# ADDER.net
KiCad netlist of a schematic drawn in Altium Designer
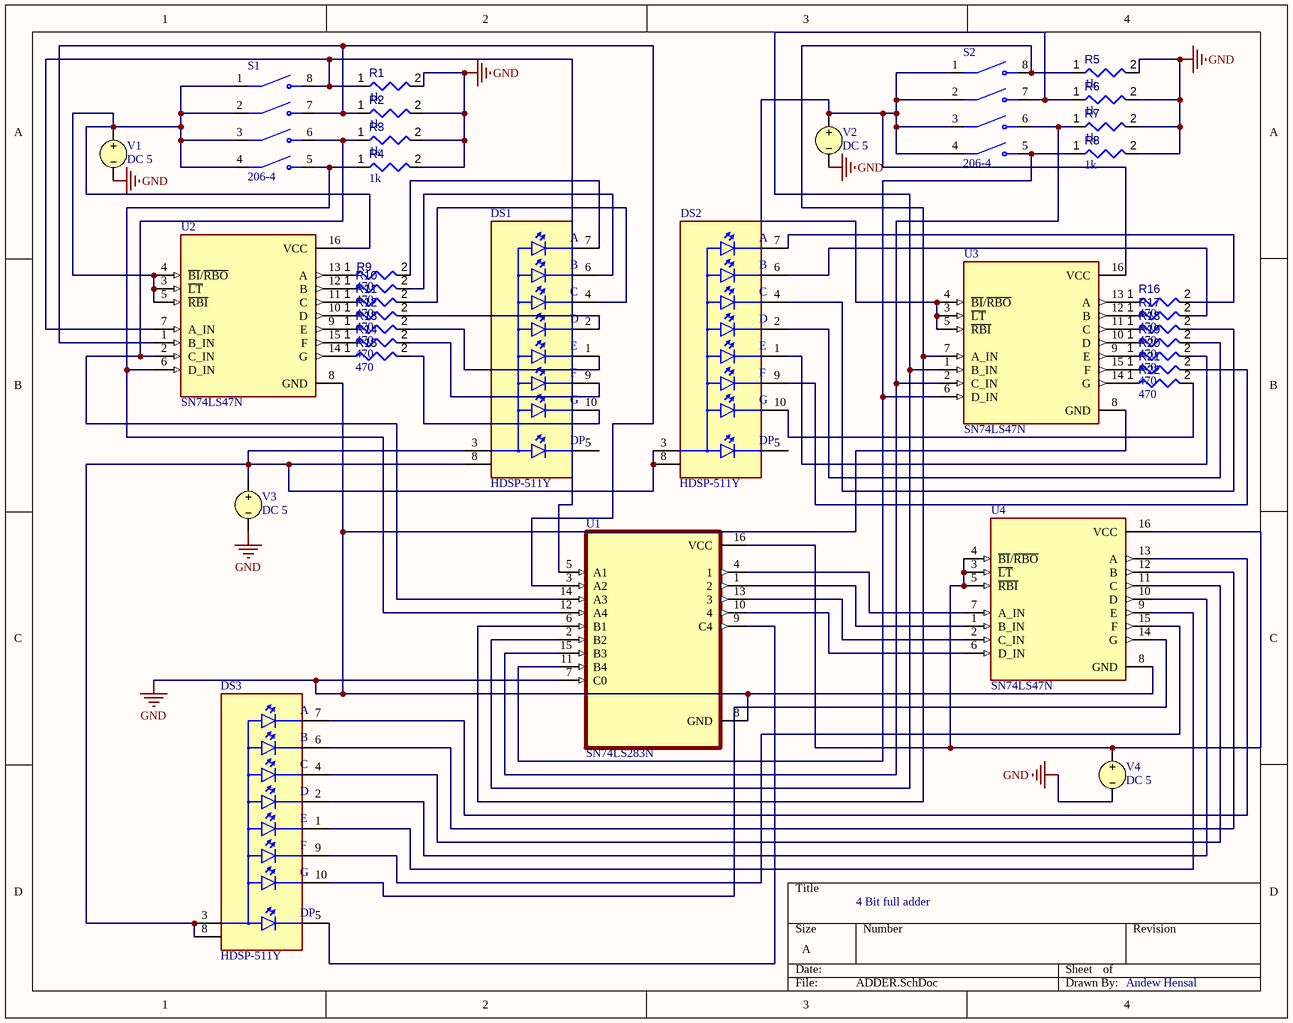
[diagram p0: ADDER.SchDoc]

(export (version "E")
  (design (tool "Eeschema 10.0.6"))
  (components
    (comp (ref "DS1")
      (value "HDSP-511Y")
      (footprint "LED_HDSP-511Y")
      (fields (field (name "MF") "Broadcom Limited"))
      (libsource (lib "HDSP-511Y") (part "HDSP-511Y"))
    )
    (comp (ref "DS2")
      (value "HDSP-511Y")
      (footprint "LED_HDSP-511Y")
      (fields (field (name "MF") "Broadcom Limited"))
      (libsource (lib "HDSP-511Y") (part "HDSP-511Y"))
    )
    (comp (ref "DS3")
      (value "HDSP-511Y")
      (footprint "LED_HDSP-511Y")
      (fields (field (name "MF") "Broadcom Limited"))
      (libsource (lib "HDSP-511Y") (part "HDSP-511Y"))
    )
    (comp (ref "R1")
      (value "1k")
      (footprint "RESC0805(2012)_L")
      (description "Chip Resistor, 1 kOhms, +/-5%, 125 mW, -55 to 155 degC, 0805")
      (fields (field (name "TOLERANCE") "5%") (field (name "POWER") "125mW"))
      (libsource (lib "Andrew Hensal") (part "RES-2"))
    )
    (comp (ref "R2")
      (value "1k")
      (footprint "RESC0805(2012)_L")
      (description "Chip Resistor, 1 kOhms, +/-5%, 125 mW, -55 to 155 degC, 0805")
      (fields (field (name "TOLERANCE") "5%") (field (name "POWER") "125mW"))
      (libsource (lib "Andrew Hensal") (part "RES-2"))
    )
    (comp (ref "R3")
      (value "1k")
      (footprint "RESC0805(2012)_L")
      (description "Chip Resistor, 1 kOhms, +/-5%, 125 mW, -55 to 155 degC, 0805")
      (fields (field (name "TOLERANCE") "5%") (field (name "POWER") "125mW"))
      (libsource (lib "Andrew Hensal") (part "RES-2"))
    )
    (comp (ref "R4")
      (value "1k")
      (footprint "RESC0805(2012)_L")
      (description "Chip Resistor, 1 kOhms, +/-5%, 125 mW, -55 to 155 degC, 0805")
      (fields (field (name "TOLERANCE") "5%") (field (name "POWER") "125mW"))
      (libsource (lib "Andrew Hensal") (part "RES-2"))
    )
    (comp (ref "R5")
      (value "1k")
      (footprint "RESC0805(2012)_L")
      (description "Chip Resistor, 1 kOhms, +/-5%, 125 mW, -55 to 155 degC, 0805")
      (fields (field (name "TOLERANCE") "5%") (field (name "POWER") "125mW"))
      (libsource (lib "Andrew Hensal") (part "RES-2"))
    )
    (comp (ref "R6")
      (value "1k")
      (footprint "RESC0805(2012)_L")
      (description "Chip Resistor, 1 kOhms, +/-5%, 125 mW, -55 to 155 degC, 0805")
      (fields (field (name "TOLERANCE") "5%") (field (name "POWER") "125mW"))
      (libsource (lib "Andrew Hensal") (part "RES-2"))
    )
    (comp (ref "R7")
      (value "1k")
      (footprint "RESC0805(2012)_L")
      (description "Chip Resistor, 1 kOhms, +/-5%, 125 mW, -55 to 155 degC, 0805")
      (fields (field (name "TOLERANCE") "5%") (field (name "POWER") "125mW"))
      (libsource (lib "Andrew Hensal") (part "RES-2"))
    )
    (comp (ref "R8")
      (value "1k")
      (footprint "RESC0805(2012)_L")
      (description "Chip Resistor, 1 kOhms, +/-5%, 125 mW, -55 to 155 degC, 0805")
      (fields (field (name "TOLERANCE") "5%") (field (name "POWER") "125mW"))
      (libsource (lib "Andrew Hensal") (part "RES-2"))
    )
    (comp (ref "R9")
      (value "470")
      (footprint "RESC0805(2012)_L")
      (description "Chip Resistor, 470 Ohms, +/-5%, 125 mW, -55 to 155 degC, 0805")
      (fields (field (name "TOLERANCE") "5%") (field (name "POWER") "125mW"))
      (libsource (lib "Andrew Hensal") (part "RES-2"))
    )
    (comp (ref "R10")
      (value "470")
      (footprint "RESC0805(2012)_L")
      (description "Chip Resistor, 470 Ohms, +/-5%, 125 mW, -55 to 155 degC, 0805")
      (fields (field (name "TOLERANCE") "5%") (field (name "POWER") "125mW"))
      (libsource (lib "Andrew Hensal") (part "RES-2"))
    )
    (comp (ref "R11")
      (value "470")
      (footprint "RESC0805(2012)_L")
      (description "Chip Resistor, 470 Ohms, +/-5%, 125 mW, -55 to 155 degC, 0805")
      (fields (field (name "TOLERANCE") "5%") (field (name "POWER") "125mW"))
      (libsource (lib "Andrew Hensal") (part "RES-2"))
    )
    (comp (ref "R12")
      (value "470")
      (footprint "RESC0805(2012)_L")
      (description "Chip Resistor, 470 Ohms, +/-5%, 125 mW, -55 to 155 degC, 0805")
      (fields (field (name "TOLERANCE") "5%") (field (name "POWER") "125mW"))
      (libsource (lib "Andrew Hensal") (part "RES-2"))
    )
    (comp (ref "R13")
      (value "470")
      (footprint "RESC0805(2012)_L")
      (description "Chip Resistor, 470 Ohms, +/-5%, 125 mW, -55 to 155 degC, 0805")
      (fields (field (name "TOLERANCE") "5%") (field (name "POWER") "125mW"))
      (libsource (lib "Andrew Hensal") (part "RES-2"))
    )
    (comp (ref "R14")
      (value "470")
      (footprint "RESC0805(2012)_L")
      (description "Chip Resistor, 470 Ohms, +/-5%, 125 mW, -55 to 155 degC, 0805")
      (fields (field (name "TOLERANCE") "5%") (field (name "POWER") "125mW"))
      (libsource (lib "Andrew Hensal") (part "RES-2"))
    )
    (comp (ref "R15")
      (value "470")
      (footprint "RESC0805(2012)_L")
      (description "Chip Resistor, 470 Ohms, +/-5%, 125 mW, -55 to 155 degC, 0805")
      (fields (field (name "TOLERANCE") "5%") (field (name "POWER") "125mW"))
      (libsource (lib "Andrew Hensal") (part "RES-2"))
    )
    (comp (ref "R16")
      (value "470")
      (footprint "RESC0805(2012)_L")
      (description "Chip Resistor, 470 Ohms, +/-5%, 125 mW, -55 to 155 degC, 0805")
      (fields (field (name "TOLERANCE") "5%") (field (name "POWER") "125mW"))
      (libsource (lib "Andrew Hensal") (part "RES-2"))
    )
    (comp (ref "R17")
      (value "470")
      (footprint "RESC0805(2012)_L")
      (description "Chip Resistor, 470 Ohms, +/-5%, 125 mW, -55 to 155 degC, 0805")
      (fields (field (name "TOLERANCE") "5%") (field (name "POWER") "125mW"))
      (libsource (lib "Andrew Hensal") (part "RES-2"))
    )
    (comp (ref "R18")
      (value "470")
      (footprint "RESC0805(2012)_L")
      (description "Chip Resistor, 470 Ohms, +/-5%, 125 mW, -55 to 155 degC, 0805")
      (fields (field (name "TOLERANCE") "5%") (field (name "POWER") "125mW"))
      (libsource (lib "Andrew Hensal") (part "RES-2"))
    )
    (comp (ref "R19")
      (value "470")
      (footprint "RESC0805(2012)_L")
      (description "Chip Resistor, 470 Ohms, +/-5%, 125 mW, -55 to 155 degC, 0805")
      (fields (field (name "TOLERANCE") "5%") (field (name "POWER") "125mW"))
      (libsource (lib "Andrew Hensal") (part "RES-2"))
    )
    (comp (ref "R20")
      (value "470")
      (footprint "RESC0805(2012)_L")
      (description "Chip Resistor, 470 Ohms, +/-5%, 125 mW, -55 to 155 degC, 0805")
      (fields (field (name "TOLERANCE") "5%") (field (name "POWER") "125mW"))
      (libsource (lib "Andrew Hensal") (part "RES-2"))
    )
    (comp (ref "R21")
      (value "470")
      (footprint "RESC0805(2012)_L")
      (description "Chip Resistor, 470 Ohms, +/-5%, 125 mW, -55 to 155 degC, 0805")
      (fields (field (name "TOLERANCE") "5%") (field (name "POWER") "125mW"))
      (libsource (lib "Andrew Hensal") (part "RES-2"))
    )
    (comp (ref "R22")
      (value "470")
      (footprint "RESC0805(2012)_L")
      (description "Chip Resistor, 470 Ohms, +/-5%, 125 mW, -55 to 155 degC, 0805")
      (fields (field (name "TOLERANCE") "5%") (field (name "POWER") "125mW"))
      (libsource (lib "Andrew Hensal") (part "RES-2"))
    )
    (comp (ref "S1")
      (value "206-4")
      (footprint "SW_206-4")
      (fields (field (name "MF") "{'manufacturer': u'CTS Components'}"))
      (libsource (lib "206-4") (part "206-4"))
    )
    (comp (ref "S2")
      (value "206-4")
      (footprint "SW_206-4")
      (fields (field (name "MF") "{'manufacturer': u'CTS Components'}"))
      (libsource (lib "206-4") (part "206-4"))
    )
    (comp (ref "U1")
      (value "SN74LS283N")
      (footprint "DIP794W45P254L1969H508Q16")
      (description "4-Bit Binary Full Adders With Fast Carry 16-PDIP 0 to 70")
      (fields (field (name "MF") "Texas Instruments"))
      (libsource (lib "SN74LS283N") (part "SN74LS283N"))
    )
    (comp (ref "U2")
      (value "SN74LS47N")
      (footprint "DIP794W45P254L1930H508Q16")
      (description "BCD-to-Seven-Segment Decoders/Drivers")
      (fields (field (name "MF") "Texas Instruments"))
      (libsource (lib "SN74LS47N") (part "SN74LS47N"))
    )
    (comp (ref "U3")
      (value "SN74LS47N")
      (footprint "DIP794W45P254L1930H508Q16")
      (description "BCD-to-Seven-Segment Decoders/Drivers")
      (fields (field (name "MF") "Texas Instruments"))
      (libsource (lib "SN74LS47N") (part "SN74LS47N"))
    )
    (comp (ref "U4")
      (value "SN74LS47N")
      (footprint "DIP794W45P254L1930H508Q16")
      (description "BCD-to-Seven-Segment Decoders/Drivers")
      (fields (field (name "MF") "Texas Instruments"))
      (libsource (lib "SN74LS47N") (part "SN74LS47N"))
    )
    (comp (ref "V1")
      (value "DC 5")
      (description "Voltage Source")
      (fields (field (name "PUBLISHER") "Altium Limited"))
      (libsource (lib "Simulation Generic Components") (part "VSRC"))
    )
    (comp (ref "V2")
      (value "DC 5")
      (description "Voltage Source")
      (fields (field (name "PUBLISHER") "Altium Limited"))
      (libsource (lib "Simulation Generic Components") (part "VSRC"))
    )
    (comp (ref "V3")
      (value "DC 5")
      (description "Voltage Source")
      (fields (field (name "PUBLISHER") "Altium Limited"))
      (libsource (lib "Simulation Generic Components") (part "VSRC"))
    )
    (comp (ref "V4")
      (value "DC 5")
      (description "Voltage Source")
      (fields (field (name "PUBLISHER") "Altium Limited"))
      (libsource (lib "Simulation Generic Components") (part "VSRC"))
    )
  )
  (nets
    (net (code "1") (name "GND") (class "Default")
      (node (ref "R1") (pin "2") (pinfunction "2_2") (pintype "passive"))
      (node (ref "R2") (pin "2") (pinfunction "2_2") (pintype "passive"))
      (node (ref "R3") (pin "2") (pinfunction "2_2") (pintype "passive"))
      (node (ref "R4") (pin "2") (pinfunction "2_2") (pintype "passive"))
      (node (ref "R5") (pin "2") (pinfunction "2_2") (pintype "passive"))
      (node (ref "R6") (pin "2") (pinfunction "2_2") (pintype "passive"))
      (node (ref "R7") (pin "2") (pinfunction "2_2") (pintype "passive"))
      (node (ref "R8") (pin "2") (pinfunction "2_2") (pintype "passive"))
      (node (ref "U1") (pin "7") (pinfunction "C0_7") (pintype "input"))
      (node (ref "U1") (pin "8") (pinfunction "GND_8") (pintype "power_in"))
      (node (ref "U2") (pin "8") (pinfunction "GND_8") (pintype "power_in"))
      (node (ref "U3") (pin "8") (pinfunction "GND_8") (pintype "power_in"))
      (node (ref "U4") (pin "8") (pinfunction "GND_8") (pintype "power_in"))
      (node (ref "V1") (pin "2") (pinfunction "2_2") (pintype "passive"))
      (node (ref "V2") (pin "2") (pinfunction "2_2") (pintype "passive"))
      (node (ref "V3") (pin "2") (pinfunction "2_2") (pintype "passive"))
      (node (ref "V4") (pin "2") (pinfunction "2_2") (pintype "passive"))
    )
    (net (code "2") (name "Net-(DS1-A)") (class "Default")
      (node (ref "DS1") (pin "7") (pinfunction "A_7") (pintype "passive"))
      (node (ref "R9") (pin "2") (pinfunction "2_2") (pintype "passive"))
    )
    (net (code "3") (name "Net-(DS1-B)") (class "Default")
      (node (ref "DS1") (pin "6") (pinfunction "B_6") (pintype "passive"))
      (node (ref "R10") (pin "2") (pinfunction "2_2") (pintype "passive"))
    )
    (net (code "4") (name "Net-(DS1-C)") (class "Default")
      (node (ref "DS1") (pin "4") (pinfunction "C_4") (pintype "passive"))
      (node (ref "R11") (pin "2") (pinfunction "2_2") (pintype "passive"))
    )
    (net (code "5") (name "Net-(DS1-COM-Pad3)") (class "Default")
      (node (ref "DS1") (pin "3") (pinfunction "COM_3") (pintype "passive"))
      (node (ref "DS1") (pin "8") (pinfunction "COM_8") (pintype "passive"))
      (node (ref "DS2") (pin "3") (pinfunction "COM_3") (pintype "passive"))
      (node (ref "DS2") (pin "8") (pinfunction "COM_8") (pintype "passive"))
      (node (ref "DS3") (pin "3") (pinfunction "COM_3") (pintype "passive"))
      (node (ref "DS3") (pin "8") (pinfunction "COM_8") (pintype "passive"))
      (node (ref "V3") (pin "1") (pinfunction "1_1") (pintype "passive"))
    )
    (net (code "6") (name "Net-(DS1-D)") (class "Default")
      (node (ref "DS1") (pin "2") (pinfunction "D_2") (pintype "passive"))
      (node (ref "R12") (pin "2") (pinfunction "2_2") (pintype "passive"))
    )
    (net (code "7") (name "Net-(DS1-E)") (class "Default")
      (node (ref "DS1") (pin "1") (pinfunction "E_1") (pintype "passive"))
      (node (ref "R13") (pin "2") (pinfunction "2_2") (pintype "passive"))
    )
    (net (code "8") (name "Net-(DS1-F)") (class "Default")
      (node (ref "DS1") (pin "9") (pinfunction "F_9") (pintype "passive"))
      (node (ref "R14") (pin "2") (pinfunction "2_2") (pintype "passive"))
    )
    (net (code "9") (name "Net-(DS1-G)") (class "Default")
      (node (ref "DS1") (pin "10") (pinfunction "G_10") (pintype "passive"))
      (node (ref "R15") (pin "2") (pinfunction "2_2") (pintype "passive"))
    )
    (net (code "10") (name "Net-(DS2-A)") (class "Default")
      (node (ref "DS2") (pin "7") (pinfunction "A_7") (pintype "passive"))
      (node (ref "R16") (pin "2") (pinfunction "2_2") (pintype "passive"))
    )
    (net (code "11") (name "Net-(DS2-B)") (class "Default")
      (node (ref "DS2") (pin "6") (pinfunction "B_6") (pintype "passive"))
      (node (ref "R17") (pin "2") (pinfunction "2_2") (pintype "passive"))
    )
    (net (code "12") (name "Net-(DS2-C)") (class "Default")
      (node (ref "DS2") (pin "4") (pinfunction "C_4") (pintype "passive"))
      (node (ref "R18") (pin "2") (pinfunction "2_2") (pintype "passive"))
    )
    (net (code "13") (name "Net-(DS2-D)") (class "Default")
      (node (ref "DS2") (pin "2") (pinfunction "D_2") (pintype "passive"))
      (node (ref "R19") (pin "2") (pinfunction "2_2") (pintype "passive"))
    )
    (net (code "14") (name "Net-(DS2-E)") (class "Default")
      (node (ref "DS2") (pin "1") (pinfunction "E_1") (pintype "passive"))
      (node (ref "R20") (pin "2") (pinfunction "2_2") (pintype "passive"))
    )
    (net (code "15") (name "Net-(DS2-F)") (class "Default")
      (node (ref "DS2") (pin "9") (pinfunction "F_9") (pintype "passive"))
      (node (ref "R21") (pin "2") (pinfunction "2_2") (pintype "passive"))
    )
    (net (code "16") (name "Net-(DS2-G)") (class "Default")
      (node (ref "DS2") (pin "10") (pinfunction "G_10") (pintype "passive"))
      (node (ref "R22") (pin "2") (pinfunction "2_2") (pintype "passive"))
    )
    (net (code "17") (name "Net-(DS3-A)") (class "Default")
      (node (ref "DS3") (pin "7") (pinfunction "A_7") (pintype "passive"))
      (node (ref "U4") (pin "13") (pinfunction "A_13") (pintype "output"))
    )
    (net (code "18") (name "Net-(DS3-B)") (class "Default")
      (node (ref "DS3") (pin "6") (pinfunction "B_6") (pintype "passive"))
      (node (ref "U4") (pin "12") (pinfunction "B_12") (pintype "output"))
    )
    (net (code "19") (name "Net-(DS3-C)") (class "Default")
      (node (ref "DS3") (pin "4") (pinfunction "C_4") (pintype "passive"))
      (node (ref "U4") (pin "11") (pinfunction "C_11") (pintype "output"))
    )
    (net (code "20") (name "Net-(DS3-D)") (class "Default")
      (node (ref "DS3") (pin "2") (pinfunction "D_2") (pintype "passive"))
      (node (ref "U4") (pin "10") (pinfunction "D_10") (pintype "output"))
    )
    (net (code "21") (name "Net-(DS3-DP)") (class "Default")
      (node (ref "DS3") (pin "5") (pinfunction "DP_5") (pintype "passive"))
      (node (ref "U1") (pin "9") (pinfunction "C4_9") (pintype "output"))
    )
    (net (code "22") (name "Net-(DS3-E)") (class "Default")
      (node (ref "DS3") (pin "1") (pinfunction "E_1") (pintype "passive"))
      (node (ref "U4") (pin "9") (pinfunction "E_9") (pintype "output"))
    )
    (net (code "23") (name "Net-(DS3-F)") (class "Default")
      (node (ref "DS3") (pin "9") (pinfunction "F_9") (pintype "passive"))
      (node (ref "U4") (pin "15") (pinfunction "F_15") (pintype "output"))
    )
    (net (code "24") (name "Net-(DS3-G)") (class "Default")
      (node (ref "DS3") (pin "10") (pinfunction "G_10") (pintype "passive"))
      (node (ref "U4") (pin "14") (pinfunction "G_14") (pintype "output"))
    )
    (net (code "25") (name "Net-(S1-COM1)") (class "Default")
      (node (ref "S1") (pin "1") (pinfunction "COM1_1") (pintype "passive"))
      (node (ref "S1") (pin "2") (pinfunction "COM2_2") (pintype "passive"))
      (node (ref "S1") (pin "3") (pinfunction "COM3_3") (pintype "passive"))
      (node (ref "S1") (pin "4") (pinfunction "COM4_4") (pintype "passive"))
      (node (ref "U2") (pin "16") (pinfunction "VCC_16") (pintype "power_in"))
      (node (ref "U2") (pin "3") (pinfunction "~{LT}_3") (pintype "input"))
      (node (ref "U2") (pin "4") (pinfunction "~{BI}/~{RBO}_4") (pintype "input"))
      (node (ref "U2") (pin "5") (pinfunction "~{RBI}_5") (pintype "input"))
      (node (ref "V1") (pin "1") (pinfunction "1_1") (pintype "passive"))
    )
    (net (code "26") (name "Net-(S1-NO1)") (class "Default")
      (node (ref "R1") (pin "1") (pinfunction "1_1") (pintype "passive"))
      (node (ref "S1") (pin "8") (pinfunction "NO1_8") (pintype "passive"))
      (node (ref "U1") (pin "5") (pinfunction "A1_5") (pintype "input"))
      (node (ref "U2") (pin "7") (pinfunction "A_IN_7") (pintype "input"))
    )
    (net (code "27") (name "Net-(S1-NO2)") (class "Default")
      (node (ref "R2") (pin "1") (pinfunction "1_1") (pintype "passive"))
      (node (ref "S1") (pin "7") (pinfunction "NO2_7") (pintype "passive"))
      (node (ref "U1") (pin "3") (pinfunction "A2_3") (pintype "input"))
      (node (ref "U2") (pin "1") (pinfunction "B_IN_1") (pintype "input"))
    )
    (net (code "28") (name "Net-(S1-NO3)") (class "Default")
      (node (ref "R3") (pin "1") (pinfunction "1_1") (pintype "passive"))
      (node (ref "S1") (pin "6") (pinfunction "NO3_6") (pintype "passive"))
      (node (ref "U1") (pin "14") (pinfunction "A3_14") (pintype "input"))
      (node (ref "U2") (pin "2") (pinfunction "C_IN_2") (pintype "input"))
    )
    (net (code "29") (name "Net-(S1-NO4)") (class "Default")
      (node (ref "R4") (pin "1") (pinfunction "1_1") (pintype "passive"))
      (node (ref "S1") (pin "5") (pinfunction "NO4_5") (pintype "passive"))
      (node (ref "U1") (pin "12") (pinfunction "A4_12") (pintype "input"))
      (node (ref "U2") (pin "6") (pinfunction "D_IN_6") (pintype "input"))
    )
    (net (code "30") (name "Net-(S2-COM1)") (class "Default")
      (node (ref "S2") (pin "1") (pinfunction "COM1_1") (pintype "passive"))
      (node (ref "S2") (pin "2") (pinfunction "COM2_2") (pintype "passive"))
      (node (ref "S2") (pin "3") (pinfunction "COM3_3") (pintype "passive"))
      (node (ref "S2") (pin "4") (pinfunction "COM4_4") (pintype "passive"))
      (node (ref "U3") (pin "16") (pinfunction "VCC_16") (pintype "power_in"))
      (node (ref "U3") (pin "3") (pinfunction "~{LT}_3") (pintype "input"))
      (node (ref "U3") (pin "4") (pinfunction "~{BI}/~{RBO}_4") (pintype "input"))
      (node (ref "U3") (pin "5") (pinfunction "~{RBI}_5") (pintype "input"))
      (node (ref "V2") (pin "1") (pinfunction "1_1") (pintype "passive"))
    )
    (net (code "31") (name "Net-(S2-NO1)") (class "Default")
      (node (ref "R5") (pin "1") (pinfunction "1_1") (pintype "passive"))
      (node (ref "S2") (pin "8") (pinfunction "NO1_8") (pintype "passive"))
      (node (ref "U1") (pin "6") (pinfunction "B1_6") (pintype "input"))
      (node (ref "U3") (pin "7") (pinfunction "A_IN_7") (pintype "input"))
    )
    (net (code "32") (name "Net-(S2-NO2)") (class "Default")
      (node (ref "R6") (pin "1") (pinfunction "1_1") (pintype "passive"))
      (node (ref "S2") (pin "7") (pinfunction "NO2_7") (pintype "passive"))
      (node (ref "U1") (pin "2") (pinfunction "B2_2") (pintype "input"))
      (node (ref "U3") (pin "1") (pinfunction "B_IN_1") (pintype "input"))
    )
    (net (code "33") (name "Net-(S2-NO3)") (class "Default")
      (node (ref "R7") (pin "1") (pinfunction "1_1") (pintype "passive"))
      (node (ref "S2") (pin "6") (pinfunction "NO3_6") (pintype "passive"))
      (node (ref "U1") (pin "15") (pinfunction "B3_15") (pintype "input"))
      (node (ref "U3") (pin "2") (pinfunction "C_IN_2") (pintype "input"))
    )
    (net (code "34") (name "Net-(S2-NO4)") (class "Default")
      (node (ref "R8") (pin "1") (pinfunction "1_1") (pintype "passive"))
      (node (ref "S2") (pin "5") (pinfunction "NO4_5") (pintype "passive"))
      (node (ref "U1") (pin "11") (pinfunction "B4_11") (pintype "input"))
      (node (ref "U3") (pin "6") (pinfunction "D_IN_6") (pintype "input"))
    )
    (net (code "35") (name "Net-(U1-1)") (class "Default")
      (node (ref "U1") (pin "4") (pinfunction "1_4") (pintype "output"))
      (node (ref "U4") (pin "7") (pinfunction "A_IN_7") (pintype "input"))
    )
    (net (code "36") (name "Net-(U1-2)") (class "Default")
      (node (ref "U1") (pin "1") (pinfunction "2_1") (pintype "output"))
      (node (ref "U4") (pin "1") (pinfunction "B_IN_1") (pintype "input"))
    )
    (net (code "37") (name "Net-(U1-3)") (class "Default")
      (node (ref "U1") (pin "13") (pinfunction "3_13") (pintype "output"))
      (node (ref "U4") (pin "2") (pinfunction "C_IN_2") (pintype "input"))
    )
    (net (code "38") (name "Net-(U1-4)") (class "Default")
      (node (ref "U1") (pin "10") (pinfunction "4_10") (pintype "output"))
      (node (ref "U4") (pin "6") (pinfunction "D_IN_6") (pintype "input"))
    )
    (net (code "39") (name "Net-(U1-VCC)") (class "Default")
      (node (ref "U1") (pin "16") (pinfunction "VCC_16") (pintype "power_in"))
      (node (ref "U4") (pin "16") (pinfunction "VCC_16") (pintype "power_in"))
      (node (ref "U4") (pin "3") (pinfunction "~{LT}_3") (pintype "input"))
      (node (ref "U4") (pin "4") (pinfunction "~{BI}/~{RBO}_4") (pintype "input"))
      (node (ref "U4") (pin "5") (pinfunction "~{RBI}_5") (pintype "input"))
      (node (ref "V4") (pin "1") (pinfunction "1_1") (pintype "passive"))
    )
    (net (code "40") (name "Net-(U2-A)") (class "Default")
      (node (ref "R9") (pin "1") (pinfunction "1_1") (pintype "passive"))
      (node (ref "U2") (pin "13") (pinfunction "A_13") (pintype "output"))
    )
    (net (code "41") (name "Net-(U2-B)") (class "Default")
      (node (ref "R10") (pin "1") (pinfunction "1_1") (pintype "passive"))
      (node (ref "U2") (pin "12") (pinfunction "B_12") (pintype "output"))
    )
    (net (code "42") (name "Net-(U2-C)") (class "Default")
      (node (ref "R11") (pin "1") (pinfunction "1_1") (pintype "passive"))
      (node (ref "U2") (pin "11") (pinfunction "C_11") (pintype "output"))
    )
    (net (code "43") (name "Net-(U2-D)") (class "Default")
      (node (ref "R12") (pin "1") (pinfunction "1_1") (pintype "passive"))
      (node (ref "U2") (pin "10") (pinfunction "D_10") (pintype "output"))
    )
    (net (code "44") (name "Net-(U2-E)") (class "Default")
      (node (ref "R13") (pin "1") (pinfunction "1_1") (pintype "passive"))
      (node (ref "U2") (pin "9") (pinfunction "E_9") (pintype "output"))
    )
    (net (code "45") (name "Net-(U2-F)") (class "Default")
      (node (ref "R14") (pin "1") (pinfunction "1_1") (pintype "passive"))
      (node (ref "U2") (pin "15") (pinfunction "F_15") (pintype "output"))
    )
    (net (code "46") (name "Net-(U2-G)") (class "Default")
      (node (ref "R15") (pin "1") (pinfunction "1_1") (pintype "passive"))
      (node (ref "U2") (pin "14") (pinfunction "G_14") (pintype "output"))
    )
    (net (code "47") (name "Net-(U3-A)") (class "Default")
      (node (ref "R16") (pin "1") (pinfunction "1_1") (pintype "passive"))
      (node (ref "U3") (pin "13") (pinfunction "A_13") (pintype "output"))
    )
    (net (code "48") (name "Net-(U3-B)") (class "Default")
      (node (ref "R17") (pin "1") (pinfunction "1_1") (pintype "passive"))
      (node (ref "U3") (pin "12") (pinfunction "B_12") (pintype "output"))
    )
    (net (code "49") (name "Net-(U3-C)") (class "Default")
      (node (ref "R18") (pin "1") (pinfunction "1_1") (pintype "passive"))
      (node (ref "U3") (pin "11") (pinfunction "C_11") (pintype "output"))
    )
    (net (code "50") (name "Net-(U3-D)") (class "Default")
      (node (ref "R19") (pin "1") (pinfunction "1_1") (pintype "passive"))
      (node (ref "U3") (pin "10") (pinfunction "D_10") (pintype "output"))
    )
    (net (code "51") (name "Net-(U3-E)") (class "Default")
      (node (ref "R20") (pin "1") (pinfunction "1_1") (pintype "passive"))
      (node (ref "U3") (pin "9") (pinfunction "E_9") (pintype "output"))
    )
    (net (code "52") (name "Net-(U3-F)") (class "Default")
      (node (ref "R21") (pin "1") (pinfunction "1_1") (pintype "passive"))
      (node (ref "U3") (pin "15") (pinfunction "F_15") (pintype "output"))
    )
    (net (code "53") (name "Net-(U3-G)") (class "Default")
      (node (ref "R22") (pin "1") (pinfunction "1_1") (pintype "passive"))
      (node (ref "U3") (pin "14") (pinfunction "G_14") (pintype "output"))
    )
    (net (code "54") (name "unconnected-(DS1-DP-Pad5)") (class "Default")
      (node (ref "DS1") (pin "5") (pinfunction "DP_5") (pintype "passive"))
    )
    (net (code "55") (name "unconnected-(DS2-DP-Pad5)") (class "Default")
      (node (ref "DS2") (pin "5") (pinfunction "DP_5") (pintype "passive"))
    )
  )
)
